# 51.net
KiCad netlist of a schematic drawn in EasyEDA Pro
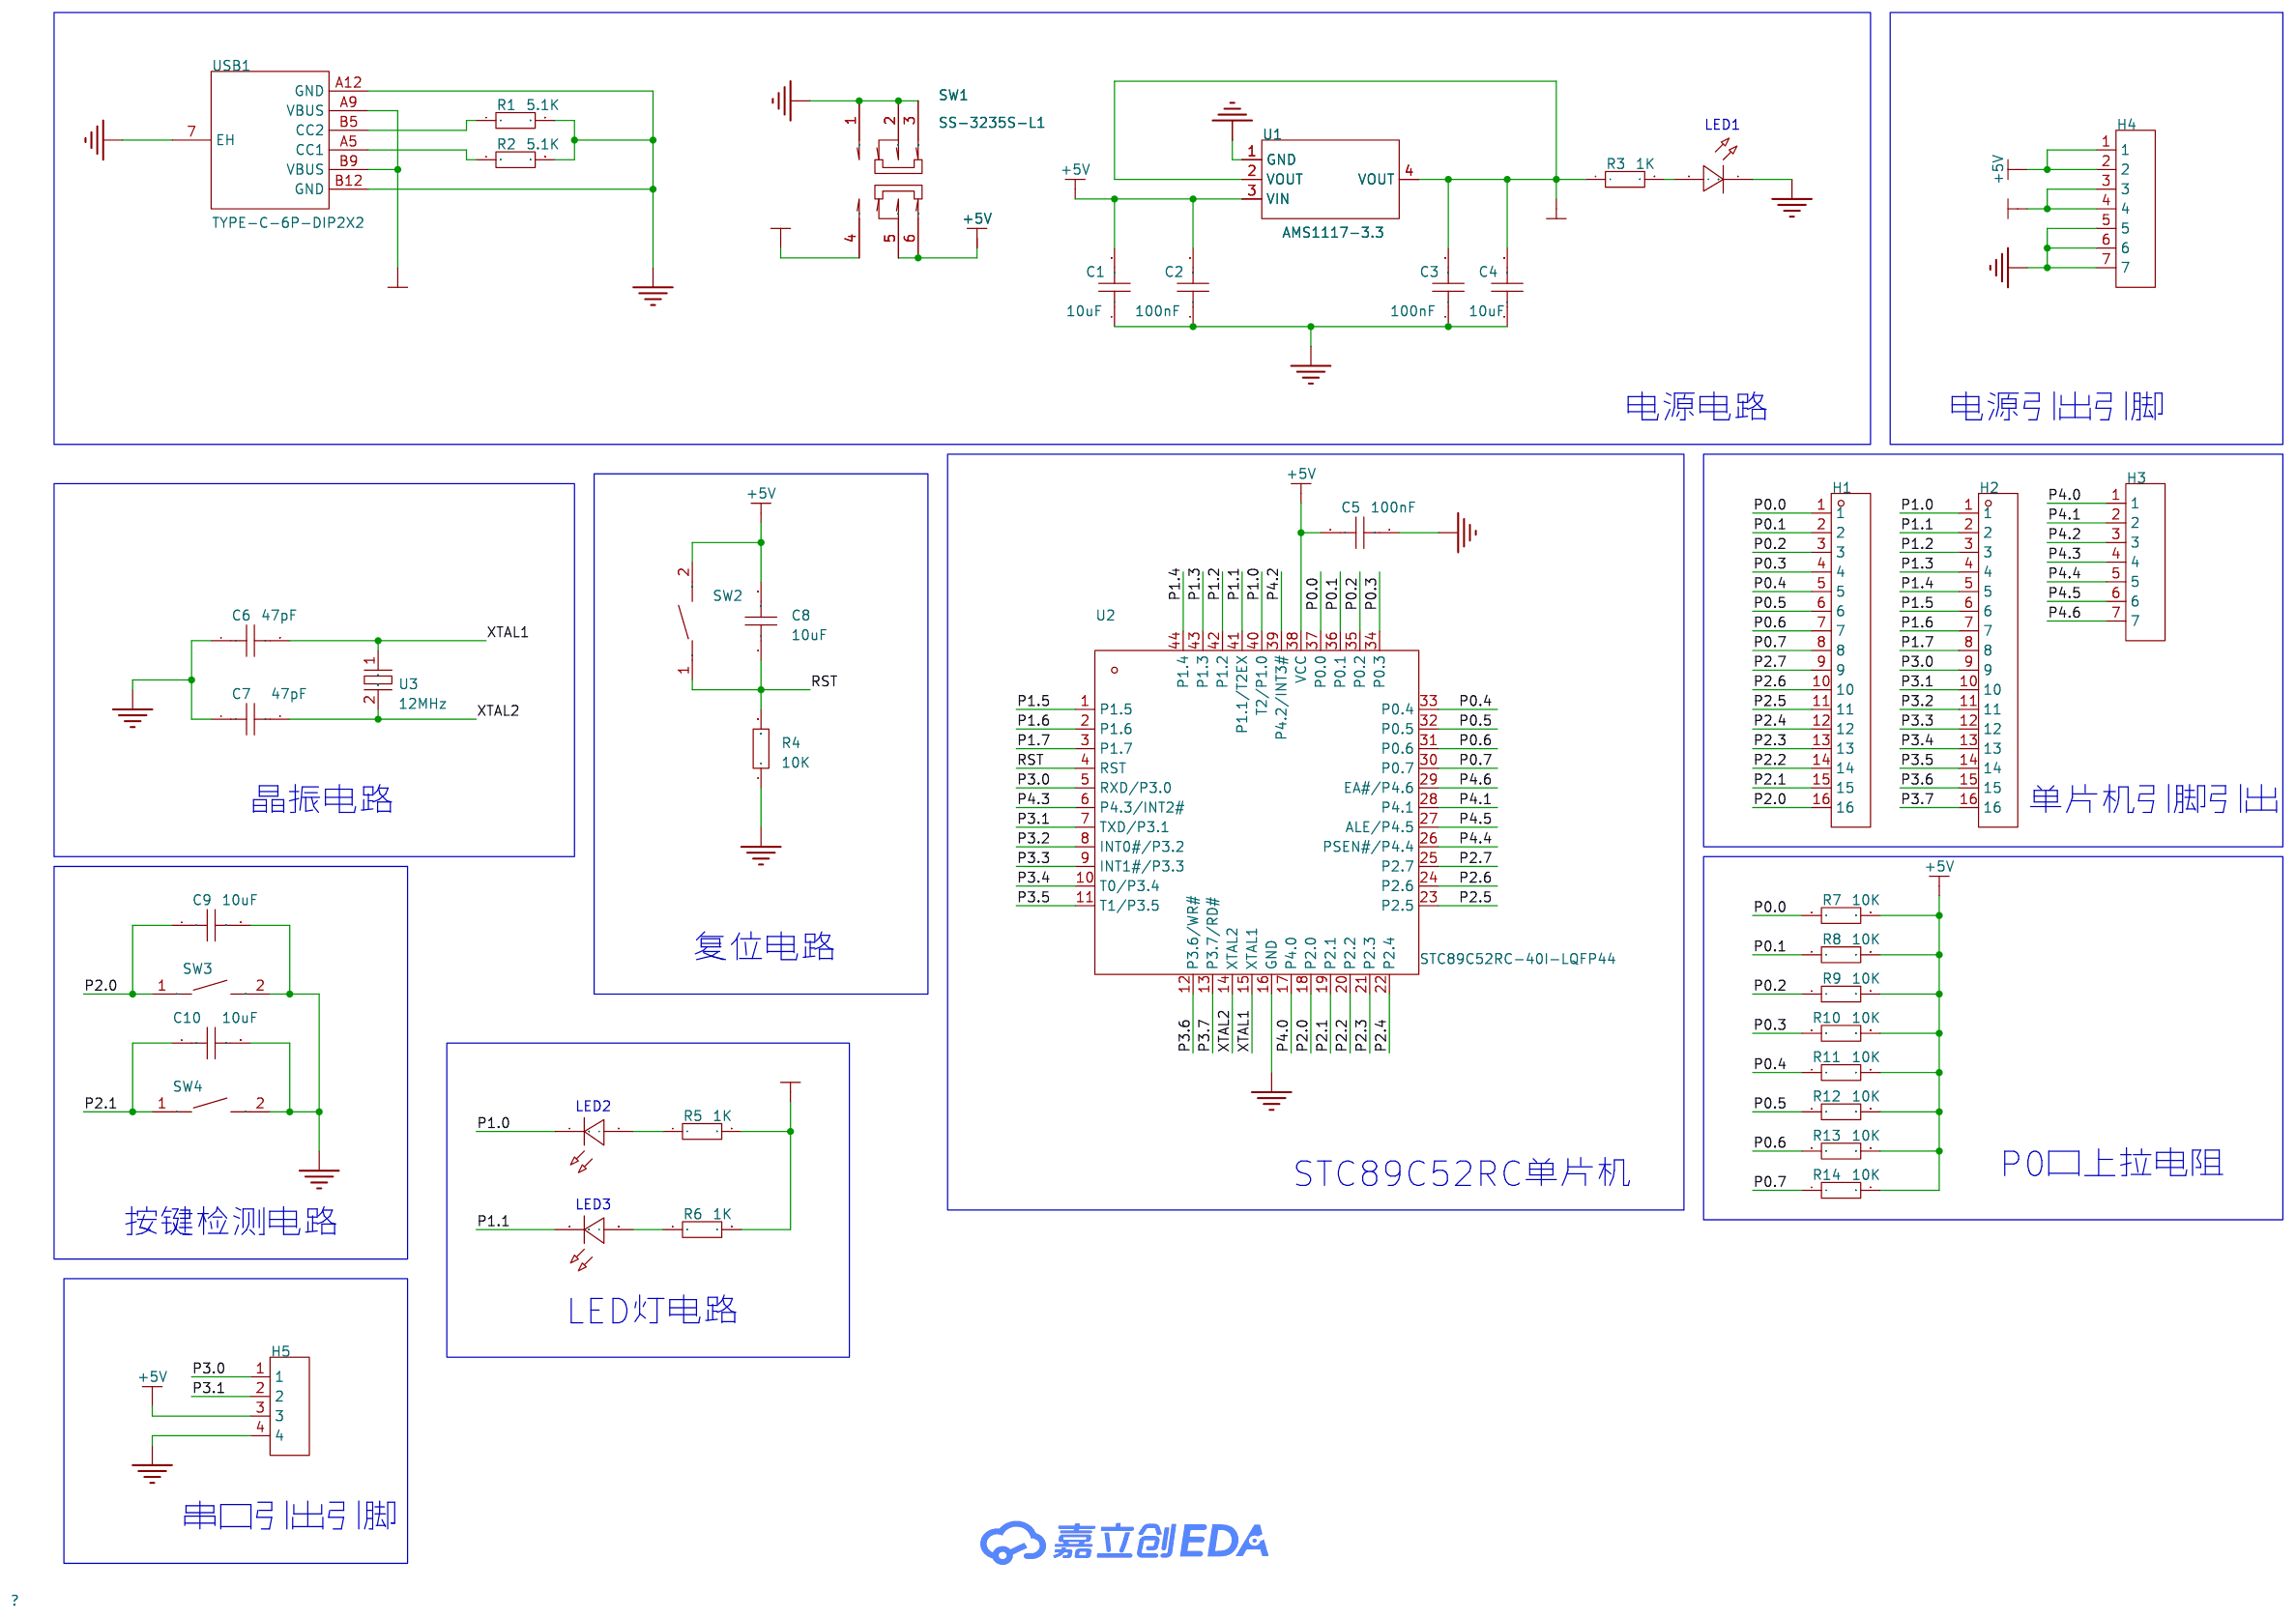
[diagram p0: schematic sheet]

(export (version "E")
  (design (tool "Eeschema 10.0.6"))
  (components
    (comp (ref "C1")
      (value "10uF")
      (footprint "easyedapro:C0805")
      (libsource (lib "easyedapro") (part "CapAcitance"))
    )
    (comp (ref "C2")
      (value "100nF")
      (footprint "easyedapro:C0805")
      (libsource (lib "easyedapro") (part "CapAcitance"))
    )
    (comp (ref "C3")
      (value "100nF")
      (footprint "easyedapro:C0805")
      (libsource (lib "easyedapro") (part "CapAcitance"))
    )
    (comp (ref "C4")
      (value "10uF")
      (footprint "easyedapro:C0805")
      (libsource (lib "easyedapro") (part "CapAcitance"))
    )
    (comp (ref "C5")
      (value "100nF")
      (footprint "easyedapro:C0805")
      (libsource (lib "easyedapro") (part "CapAcitance"))
    )
    (comp (ref "C6")
      (value "47pF")
      (footprint "easyedapro:C0805")
      (libsource (lib "easyedapro") (part "CapAcitance"))
    )
    (comp (ref "C7")
      (value "47pF")
      (footprint "easyedapro:C0805")
      (libsource (lib "easyedapro") (part "CapAcitance"))
    )
    (comp (ref "C8")
      (value "10uF")
      (footprint "easyedapro:C0805")
      (libsource (lib "easyedapro") (part "CapAcitance"))
    )
    (comp (ref "C9")
      (value "10uF")
      (footprint "easyedapro:C0805")
      (libsource (lib "easyedapro") (part "CapAcitance"))
    )
    (comp (ref "C10")
      (value "10uF")
      (footprint "easyedapro:C0805")
      (libsource (lib "easyedapro") (part "CapAcitance"))
    )
    (comp (ref "H1")
      (value "~")
      (footprint "easyedapro:HDR-TH_16P-P2.54-V-M")
      (libsource (lib "easyedapro") (part "HDR_2.54-1x16P"))
    )
    (comp (ref "H2")
      (value "~")
      (footprint "easyedapro:HDR-TH_16P-P2.54-V-M")
      (libsource (lib "easyedapro") (part "HDR_2.54-1x16P"))
    )
    (comp (ref "H3")
      (value "~")
      (footprint "easyedapro:HDR-TH_7P-P2.54-V-M")
      (libsource (lib "easyedapro") (part "PZ254V-11-07P"))
    )
    (comp (ref "H4")
      (value "~")
      (footprint "easyedapro:HDR-TH_7P-P2.54-V-M")
      (libsource (lib "easyedapro") (part "PZ254V-11-07P"))
    )
    (comp (ref "H5")
      (value "~")
      (footprint "easyedapro:HDR-TH_4P-P2.54-V-M")
      (libsource (lib "easyedapro") (part "PZ254V-11-04P"))
    )
    (comp (ref "LED1")
      (value "~")
      (footprint "easyedapro:LED_0805")
      (libsource (lib "easyedapro") (part "LED_G"))
    )
    (comp (ref "LED2")
      (value "~")
      (footprint "easyedapro:LED_0805")
      (libsource (lib "easyedapro") (part "LED_G"))
    )
    (comp (ref "LED3")
      (value "~")
      (footprint "easyedapro:LED_0805")
      (libsource (lib "easyedapro") (part "LED_G"))
    )
    (comp (ref "R1") (value "5.1K") (footprint "easyedapro:R0805") (libsource (lib "easyedapro") (part "电阻")))
    (comp (ref "R2") (value "5.1K") (footprint "easyedapro:R0805") (libsource (lib "easyedapro") (part "电阻")))
    (comp (ref "R3") (value "1K") (footprint "easyedapro:R0805") (libsource (lib "easyedapro") (part "电阻")))
    (comp (ref "R4") (value "10K") (footprint "easyedapro:R0805") (libsource (lib "easyedapro") (part "电阻")))
    (comp (ref "R5") (value "1K") (footprint "easyedapro:R0805") (libsource (lib "easyedapro") (part "电阻")))
    (comp (ref "R6") (value "1K") (footprint "easyedapro:R0805") (libsource (lib "easyedapro") (part "电阻")))
    (comp (ref "R7") (value "10K") (footprint "easyedapro:R0805") (libsource (lib "easyedapro") (part "电阻")))
    (comp (ref "R8") (value "10K") (footprint "easyedapro:R0805") (libsource (lib "easyedapro") (part "电阻")))
    (comp (ref "R9") (value "10K") (footprint "easyedapro:R0805") (libsource (lib "easyedapro") (part "电阻")))
    (comp (ref "R10") (value "10K") (footprint "easyedapro:R0805") (libsource (lib "easyedapro") (part "电阻")))
    (comp (ref "R11") (value "10K") (footprint "easyedapro:R0805") (libsource (lib "easyedapro") (part "电阻")))
    (comp (ref "R12") (value "10K") (footprint "easyedapro:R0805") (libsource (lib "easyedapro") (part "电阻")))
    (comp (ref "R13") (value "10K") (footprint "easyedapro:R0805") (libsource (lib "easyedapro") (part "电阻")))
    (comp (ref "R14") (value "10K") (footprint "easyedapro:R0805") (libsource (lib "easyedapro") (part "电阻")))
    (comp (ref "SW1")
      (value "SS-3235S-L1")
      (footprint "easyedapro:SW-SMD_SS-3235S-LX")
      (description "电路结构:双刀双掷;安装方式:卧贴;开关颜色:黑色;额定电流(DC):50mA;额定电压(DC):12V;额定电流(AC):50mA;额定电压(AC):12V;机械寿命:1万次;")
      (fields (field (name "Manufacturer") "XKB Connectivity(中国星坤)"))
      (libsource (lib "easyedapro") (part "SS-3235S-L1"))
    )
    (comp (ref "SW2")
      (value "轻触按键3*4*H")
      (footprint "easyedapro:SW-SMD_L4.0-W2.9-LS5.0")
      (libsource (lib "easyedapro") (part "轻触按键3*4*H"))
    )
    (comp (ref "SW3")
      (value "轻触按键3*4*H")
      (footprint "easyedapro:SW-SMD_L4.0-W2.9-LS5.0")
      (libsource (lib "easyedapro") (part "轻触按键3*4*H"))
    )
    (comp (ref "SW4")
      (value "轻触按键3*4*H")
      (footprint "easyedapro:SW-SMD_L4.0-W2.9-LS5.0")
      (libsource (lib "easyedapro") (part "轻触按键3*4*H"))
    )
    (comp (ref "U1")
      (value "AMS1117-3.3")
      (footprint "easyedapro:SOT-223-3_L6.5-W3.4-P2.30-LS7.0-BR")
      (description "输出类型:固定;工作电压:-;输出电压:3.3V;输出电流:1A;电源纹波抑制比(PSRR):72dB@(120Hz);输出极性:正极;")
      (fields (field (name "Manufacturer") "AMS"))
      (libsource (lib "easyedapro") (part "AMS1117-3.3"))
    )
    (comp (ref "U2")
      (value "STC89C52RC-40I-LQFP44")
      (footprint "easyedapro:LQFP-44_L10.0-W10.0-P0.80-LS12.0-BL")
      (description "CPU内核:51系列;应用领域:-;")
      (fields (field (name "Manufacturer") "STC"))
      (libsource (lib "easyedapro") (part "STC89C52RC-40I_C8707"))
    )
    (comp (ref "U3")
      (value "12MHz")
      (footprint "easyedapro:CRYSTAL-SMD_L11.4-W4.7-LS12.7")
      (description "频率:12MHz;常温频差:±30ppm;外接负载电容:18pF;频率稳定度(全温):±35ppm;")
      (fields
        (field (name "Manufacturer Part") "ABLS-12.000MHZ-B4H-T")
        (field (name "Manufacturer") "ABRACON")
      )
      (libsource (lib "easyedapro") (part "ABLS-12.000MHZ-B4H-T"))
    )
    (comp (ref "USB1")
      (value "TYPE-C-6P-DIP2X2")
      (footprint "easyedapro:TYPE-C-SMD_TYPE-C-6P")
      (libsource (lib "easyedapro") (part "TYPE-C-6P-DIP2X2"))
    )
  )
  (nets
    (net (code "1") (name "+5V") (class "Default")
      (node (ref "C1") (pin "2") (pinfunction "2_2") (pintype "input"))
      (node (ref "C2") (pin "2") (pinfunction "2_2") (pintype "input"))
      (node (ref "C5") (pin "2") (pinfunction "2_2") (pintype "input"))
      (node (ref "C8") (pin "2") (pinfunction "2_2") (pintype "input"))
      (node (ref "H4") (pin "1") (pinfunction "1_1") (pintype "unspecified"))
      (node (ref "H4") (pin "2") (pinfunction "2_2") (pintype "unspecified"))
      (node (ref "H5") (pin "3") (pinfunction "3_3") (pintype "unspecified"))
      (node (ref "R10") (pin "2") (pinfunction "2_2") (pintype "input"))
      (node (ref "R11") (pin "2") (pinfunction "2_2") (pintype "input"))
      (node (ref "R12") (pin "2") (pinfunction "2_2") (pintype "input"))
      (node (ref "R13") (pin "2") (pinfunction "2_2") (pintype "input"))
      (node (ref "R14") (pin "2") (pinfunction "2_2") (pintype "input"))
      (node (ref "R7") (pin "2") (pinfunction "2_2") (pintype "input"))
      (node (ref "R8") (pin "2") (pinfunction "2_2") (pintype "input"))
      (node (ref "R9") (pin "2") (pinfunction "2_2") (pintype "input"))
      (node (ref "SW1") (pin "5") (pinfunction "5_5") (pintype "unspecified"))
      (node (ref "SW1") (pin "6") (pinfunction "6_6") (pintype "unspecified"))
      (node (ref "SW2") (pin "2") (pinfunction "2_2") (pintype "unspecified"))
      (node (ref "U1") (pin "3") (pinfunction "VIN_3") (pintype "unspecified"))
      (node (ref "U2") (pin "38") (pinfunction "VCC_38") (pintype "unspecified"))
    )
    (net (code "2") (name "/P0.0") (class "Default")
      (node (ref "H1") (pin "1") (pinfunction "1_1") (pintype "input"))
      (node (ref "R7") (pin "1") (pinfunction "1_1") (pintype "input"))
      (node (ref "U2") (pin "37") (pinfunction "P0.0_37") (pintype "unspecified"))
    )
    (net (code "3") (name "/P0.1") (class "Default")
      (node (ref "H1") (pin "2") (pinfunction "2_2") (pintype "input"))
      (node (ref "R8") (pin "1") (pinfunction "1_1") (pintype "input"))
      (node (ref "U2") (pin "36") (pinfunction "P0.1_36") (pintype "unspecified"))
    )
    (net (code "4") (name "/P0.2") (class "Default")
      (node (ref "H1") (pin "3") (pinfunction "3_3") (pintype "input"))
      (node (ref "R9") (pin "1") (pinfunction "1_1") (pintype "input"))
      (node (ref "U2") (pin "35") (pinfunction "P0.2_35") (pintype "unspecified"))
    )
    (net (code "5") (name "/P0.3") (class "Default")
      (node (ref "H1") (pin "4") (pinfunction "4_4") (pintype "input"))
      (node (ref "R10") (pin "1") (pinfunction "1_1") (pintype "input"))
      (node (ref "U2") (pin "34") (pinfunction "P0.3_34") (pintype "unspecified"))
    )
    (net (code "6") (name "/P0.4") (class "Default")
      (node (ref "H1") (pin "5") (pinfunction "5_5") (pintype "input"))
      (node (ref "R11") (pin "1") (pinfunction "1_1") (pintype "input"))
      (node (ref "U2") (pin "33") (pinfunction "P0.4_33") (pintype "unspecified"))
    )
    (net (code "7") (name "/P0.5") (class "Default")
      (node (ref "H1") (pin "6") (pinfunction "6_6") (pintype "input"))
      (node (ref "R12") (pin "1") (pinfunction "1_1") (pintype "input"))
      (node (ref "U2") (pin "32") (pinfunction "P0.5_32") (pintype "unspecified"))
    )
    (net (code "8") (name "/P0.6") (class "Default")
      (node (ref "H1") (pin "7") (pinfunction "7_7") (pintype "input"))
      (node (ref "R13") (pin "1") (pinfunction "1_1") (pintype "input"))
      (node (ref "U2") (pin "31") (pinfunction "P0.6_31") (pintype "unspecified"))
    )
    (net (code "9") (name "/P0.7") (class "Default")
      (node (ref "H1") (pin "8") (pinfunction "8_8") (pintype "input"))
      (node (ref "R14") (pin "1") (pinfunction "1_1") (pintype "input"))
      (node (ref "U2") (pin "30") (pinfunction "P0.7_30") (pintype "unspecified"))
    )
    (net (code "10") (name "/P1.0") (class "Default")
      (node (ref "H2") (pin "1") (pinfunction "1_1") (pintype "input"))
      (node (ref "LED2") (pin "1") (pinfunction "C_1") (pintype "input"))
      (node (ref "U2") (pin "40") (pinfunction "T2/P1.0_40") (pintype "unspecified"))
    )
    (net (code "11") (name "/P1.1") (class "Default")
      (node (ref "H2") (pin "2") (pinfunction "2_2") (pintype "input"))
      (node (ref "LED3") (pin "1") (pinfunction "C_1") (pintype "input"))
      (node (ref "U2") (pin "41") (pinfunction "P1.1/T2EX_41") (pintype "unspecified"))
    )
    (net (code "12") (name "/P1.2") (class "Default")
      (node (ref "H2") (pin "3") (pinfunction "3_3") (pintype "input"))
      (node (ref "U2") (pin "42") (pinfunction "P1.2_42") (pintype "unspecified"))
    )
    (net (code "13") (name "/P1.3") (class "Default")
      (node (ref "H2") (pin "4") (pinfunction "4_4") (pintype "input"))
      (node (ref "U2") (pin "43") (pinfunction "P1.3_43") (pintype "unspecified"))
    )
    (net (code "14") (name "/P1.4") (class "Default")
      (node (ref "H2") (pin "5") (pinfunction "5_5") (pintype "input"))
      (node (ref "U2") (pin "44") (pinfunction "P1.4_44") (pintype "unspecified"))
    )
    (net (code "15") (name "/P1.5") (class "Default")
      (node (ref "H2") (pin "6") (pinfunction "6_6") (pintype "input"))
      (node (ref "U2") (pin "1") (pinfunction "P1.5_1") (pintype "unspecified"))
    )
    (net (code "16") (name "/P1.6") (class "Default")
      (node (ref "H2") (pin "7") (pinfunction "7_7") (pintype "input"))
      (node (ref "U2") (pin "2") (pinfunction "P1.6_2") (pintype "unspecified"))
    )
    (net (code "17") (name "/P1.7") (class "Default")
      (node (ref "H2") (pin "8") (pinfunction "8_8") (pintype "input"))
      (node (ref "U2") (pin "3") (pinfunction "P1.7_3") (pintype "unspecified"))
    )
    (net (code "18") (name "/P2.0") (class "Default")
      (node (ref "C9") (pin "1") (pinfunction "1_1") (pintype "input"))
      (node (ref "H1") (pin "16") (pinfunction "16_16") (pintype "input"))
      (node (ref "SW3") (pin "1") (pinfunction "1_1") (pintype "unspecified"))
      (node (ref "U2") (pin "18") (pinfunction "P2.0_18") (pintype "unspecified"))
    )
    (net (code "19") (name "/P2.1") (class "Default")
      (node (ref "C10") (pin "1") (pinfunction "1_1") (pintype "input"))
      (node (ref "H1") (pin "15") (pinfunction "15_15") (pintype "input"))
      (node (ref "SW4") (pin "1") (pinfunction "1_1") (pintype "unspecified"))
      (node (ref "U2") (pin "19") (pinfunction "P2.1_19") (pintype "unspecified"))
    )
    (net (code "20") (name "/P2.2") (class "Default")
      (node (ref "H1") (pin "14") (pinfunction "14_14") (pintype "input"))
      (node (ref "U2") (pin "20") (pinfunction "P2.2_20") (pintype "unspecified"))
    )
    (net (code "21") (name "/P2.3") (class "Default")
      (node (ref "H1") (pin "13") (pinfunction "13_13") (pintype "input"))
      (node (ref "U2") (pin "21") (pinfunction "P2.3_21") (pintype "unspecified"))
    )
    (net (code "22") (name "/P2.4") (class "Default")
      (node (ref "H1") (pin "12") (pinfunction "12_12") (pintype "input"))
      (node (ref "U2") (pin "22") (pinfunction "P2.4_22") (pintype "unspecified"))
    )
    (net (code "23") (name "/P2.5") (class "Default")
      (node (ref "H1") (pin "11") (pinfunction "11_11") (pintype "input"))
      (node (ref "U2") (pin "23") (pinfunction "P2.5_23") (pintype "unspecified"))
    )
    (net (code "24") (name "/P2.6") (class "Default")
      (node (ref "H1") (pin "10") (pinfunction "10_10") (pintype "input"))
      (node (ref "U2") (pin "24") (pinfunction "P2.6_24") (pintype "unspecified"))
    )
    (net (code "25") (name "/P2.7") (class "Default")
      (node (ref "H1") (pin "9") (pinfunction "9_9") (pintype "input"))
      (node (ref "U2") (pin "25") (pinfunction "P2.7_25") (pintype "unspecified"))
    )
    (net (code "26") (name "/P3.0") (class "Default")
      (node (ref "H2") (pin "9") (pinfunction "9_9") (pintype "input"))
      (node (ref "H5") (pin "1") (pinfunction "1_1") (pintype "unspecified"))
      (node (ref "U2") (pin "5") (pinfunction "RXD/P3.0_5") (pintype "unspecified"))
    )
    (net (code "27") (name "/P3.1") (class "Default")
      (node (ref "H2") (pin "10") (pinfunction "10_10") (pintype "input"))
      (node (ref "H5") (pin "2") (pinfunction "2_2") (pintype "unspecified"))
      (node (ref "U2") (pin "7") (pinfunction "TXD/P3.1_7") (pintype "unspecified"))
    )
    (net (code "28") (name "/P3.2") (class "Default")
      (node (ref "H2") (pin "11") (pinfunction "11_11") (pintype "input"))
      (node (ref "U2") (pin "8") (pinfunction "INT0#/P3.2_8") (pintype "unspecified"))
    )
    (net (code "29") (name "/P3.3") (class "Default")
      (node (ref "H2") (pin "12") (pinfunction "12_12") (pintype "input"))
      (node (ref "U2") (pin "9") (pinfunction "INT1#/P3.3_9") (pintype "unspecified"))
    )
    (net (code "30") (name "/P3.4") (class "Default")
      (node (ref "H2") (pin "13") (pinfunction "13_13") (pintype "input"))
      (node (ref "U2") (pin "10") (pinfunction "T0/P3.4_10") (pintype "unspecified"))
    )
    (net (code "31") (name "/P3.5") (class "Default")
      (node (ref "H2") (pin "14") (pinfunction "14_14") (pintype "input"))
      (node (ref "U2") (pin "11") (pinfunction "T1/P3.5_11") (pintype "unspecified"))
    )
    (net (code "32") (name "/P3.6") (class "Default")
      (node (ref "H2") (pin "15") (pinfunction "15_15") (pintype "input"))
      (node (ref "U2") (pin "12") (pinfunction "P3.6/WR#_12") (pintype "unspecified"))
    )
    (net (code "33") (name "/P3.7") (class "Default")
      (node (ref "H2") (pin "16") (pinfunction "16_16") (pintype "input"))
      (node (ref "U2") (pin "13") (pinfunction "P3.7/RD#_13") (pintype "unspecified"))
    )
    (net (code "34") (name "/P4.0") (class "Default")
      (node (ref "H3") (pin "1") (pinfunction "1_1") (pintype "unspecified"))
      (node (ref "U2") (pin "17") (pinfunction "P4.0_17") (pintype "unspecified"))
    )
    (net (code "35") (name "/P4.1") (class "Default")
      (node (ref "H3") (pin "2") (pinfunction "2_2") (pintype "unspecified"))
      (node (ref "U2") (pin "28") (pinfunction "P4.1_28") (pintype "unspecified"))
    )
    (net (code "36") (name "/P4.2") (class "Default")
      (node (ref "H3") (pin "3") (pinfunction "3_3") (pintype "unspecified"))
      (node (ref "U2") (pin "39") (pinfunction "P4.2/INT3#_39") (pintype "unspecified"))
    )
    (net (code "37") (name "/P4.3") (class "Default")
      (node (ref "H3") (pin "4") (pinfunction "4_4") (pintype "unspecified"))
      (node (ref "U2") (pin "6") (pinfunction "P4.3/INT2#_6") (pintype "unspecified"))
    )
    (net (code "38") (name "/P4.4") (class "Default")
      (node (ref "H3") (pin "5") (pinfunction "5_5") (pintype "unspecified"))
      (node (ref "U2") (pin "26") (pinfunction "PSEN#/P4.4_26") (pintype "unspecified"))
    )
    (net (code "39") (name "/P4.5") (class "Default")
      (node (ref "H3") (pin "6") (pinfunction "6_6") (pintype "unspecified"))
      (node (ref "U2") (pin "27") (pinfunction "ALE/P4.5_27") (pintype "unspecified"))
    )
    (net (code "40") (name "/P4.6") (class "Default")
      (node (ref "H3") (pin "7") (pinfunction "7_7") (pintype "unspecified"))
      (node (ref "U2") (pin "29") (pinfunction "EA#/P4.6_29") (pintype "unspecified"))
    )
    (net (code "41") (name "/RST") (class "Default")
      (node (ref "C8") (pin "1") (pinfunction "1_1") (pintype "input"))
      (node (ref "R4") (pin "2") (pinfunction "2_2") (pintype "input"))
      (node (ref "SW2") (pin "1") (pinfunction "1_1") (pintype "unspecified"))
      (node (ref "U2") (pin "4") (pinfunction "RST_4") (pintype "unspecified"))
    )
    (net (code "42") (name "/XTAL1") (class "Default")
      (node (ref "C6") (pin "2") (pinfunction "2_2") (pintype "input"))
      (node (ref "U2") (pin "15") (pinfunction "XTAL1_15") (pintype "unspecified"))
      (node (ref "U3") (pin "1") (pinfunction "1_1") (pintype "input"))
    )
    (net (code "43") (name "/XTAL2") (class "Default")
      (node (ref "C7") (pin "2") (pinfunction "2_2") (pintype "input"))
      (node (ref "U2") (pin "14") (pinfunction "XTAL2_14") (pintype "unspecified"))
      (node (ref "U3") (pin "2") (pinfunction "GND_2") (pintype "input"))
    )
    (net (code "44") (name "3.3V") (class "Default")
      (node (ref "C3") (pin "2") (pinfunction "2_2") (pintype "input"))
      (node (ref "C4") (pin "2") (pinfunction "2_2") (pintype "input"))
      (node (ref "H4") (pin "3") (pinfunction "3_3") (pintype "unspecified"))
      (node (ref "H4") (pin "4") (pinfunction "4_4") (pintype "unspecified"))
      (node (ref "R3") (pin "1") (pinfunction "1_1") (pintype "input"))
      (node (ref "R5") (pin "2") (pinfunction "2_2") (pintype "input"))
      (node (ref "R6") (pin "2") (pinfunction "2_2") (pintype "input"))
      (node (ref "U1") (pin "2") (pinfunction "VOUT_2") (pintype "unspecified"))
      (node (ref "U1") (pin "4") (pinfunction "VOUT_4") (pintype "unspecified"))
    )
    (net (code "45") (name "GND") (class "Default")
      (node (ref "C1") (pin "1") (pinfunction "1_1") (pintype "input"))
      (node (ref "C10") (pin "2") (pinfunction "2_2") (pintype "input"))
      (node (ref "C2") (pin "1") (pinfunction "1_1") (pintype "input"))
      (node (ref "C3") (pin "1") (pinfunction "1_1") (pintype "input"))
      (node (ref "C4") (pin "1") (pinfunction "1_1") (pintype "input"))
      (node (ref "C5") (pin "1") (pinfunction "1_1") (pintype "input"))
      (node (ref "C6") (pin "1") (pinfunction "1_1") (pintype "input"))
      (node (ref "C7") (pin "1") (pinfunction "1_1") (pintype "input"))
      (node (ref "C9") (pin "2") (pinfunction "2_2") (pintype "input"))
      (node (ref "H4") (pin "5") (pinfunction "5_5") (pintype "unspecified"))
      (node (ref "H4") (pin "6") (pinfunction "6_6") (pintype "unspecified"))
      (node (ref "H4") (pin "7") (pinfunction "7_7") (pintype "unspecified"))
      (node (ref "H5") (pin "4") (pinfunction "4_4") (pintype "unspecified"))
      (node (ref "LED1") (pin "1") (pinfunction "C_1") (pintype "input"))
      (node (ref "R1") (pin "2") (pinfunction "2_2") (pintype "input"))
      (node (ref "R2") (pin "2") (pinfunction "2_2") (pintype "input"))
      (node (ref "R4") (pin "1") (pinfunction "1_1") (pintype "input"))
      (node (ref "SW1") (pin "1") (pinfunction "1_1") (pintype "unspecified"))
      (node (ref "SW1") (pin "2") (pinfunction "2_2") (pintype "unspecified"))
      (node (ref "SW1") (pin "3") (pinfunction "3_3") (pintype "unspecified"))
      (node (ref "SW3") (pin "2") (pinfunction "2_2") (pintype "unspecified"))
      (node (ref "SW4") (pin "2") (pinfunction "2_2") (pintype "unspecified"))
      (node (ref "U1") (pin "1") (pinfunction "GND_1") (pintype "unspecified"))
      (node (ref "U2") (pin "16") (pinfunction "GND_16") (pintype "unspecified"))
      (node (ref "USB1") (pin "7") (pinfunction "EH_7") (pintype "unspecified"))
      (node (ref "USB1") (pin "A12") (pinfunction "GND_A12") (pintype "unspecified"))
      (node (ref "USB1") (pin "B12") (pinfunction "GND_B12") (pintype "unspecified"))
    )
    (net (code "46") (name "Net-(LED1-A)") (class "Default")
      (node (ref "LED1") (pin "2") (pinfunction "A_2") (pintype "input"))
      (node (ref "R3") (pin "2") (pinfunction "2_2") (pintype "input"))
    )
    (net (code "47") (name "Net-(LED2-A)") (class "Default")
      (node (ref "LED2") (pin "2") (pinfunction "A_2") (pintype "input"))
      (node (ref "R5") (pin "1") (pinfunction "1_1") (pintype "input"))
    )
    (net (code "48") (name "Net-(LED3-A)") (class "Default")
      (node (ref "LED3") (pin "2") (pinfunction "A_2") (pintype "input"))
      (node (ref "R6") (pin "1") (pinfunction "1_1") (pintype "input"))
    )
    (net (code "49") (name "Net-(USB1-CC1)") (class "Default")
      (node (ref "R2") (pin "1") (pinfunction "1_1") (pintype "input"))
      (node (ref "USB1") (pin "A5") (pinfunction "CC1_A5") (pintype "unspecified"))
    )
    (net (code "50") (name "Net-(USB1-CC2)") (class "Default")
      (node (ref "R1") (pin "1") (pinfunction "1_1") (pintype "input"))
      (node (ref "USB1") (pin "B5") (pinfunction "CC2_B5") (pintype "unspecified"))
    )
    (net (code "51") (name "VCC+5V") (class "Default")
      (node (ref "SW1") (pin "4") (pinfunction "4_4") (pintype "unspecified"))
      (node (ref "USB1") (pin "A9") (pinfunction "VBUS_A9") (pintype "unspecified"))
      (node (ref "USB1") (pin "B9") (pinfunction "VBUS_B9") (pintype "unspecified"))
    )
  )
)
